# mainboard_v1.net
KiCad netlist of a schematic drawn in EAGLE
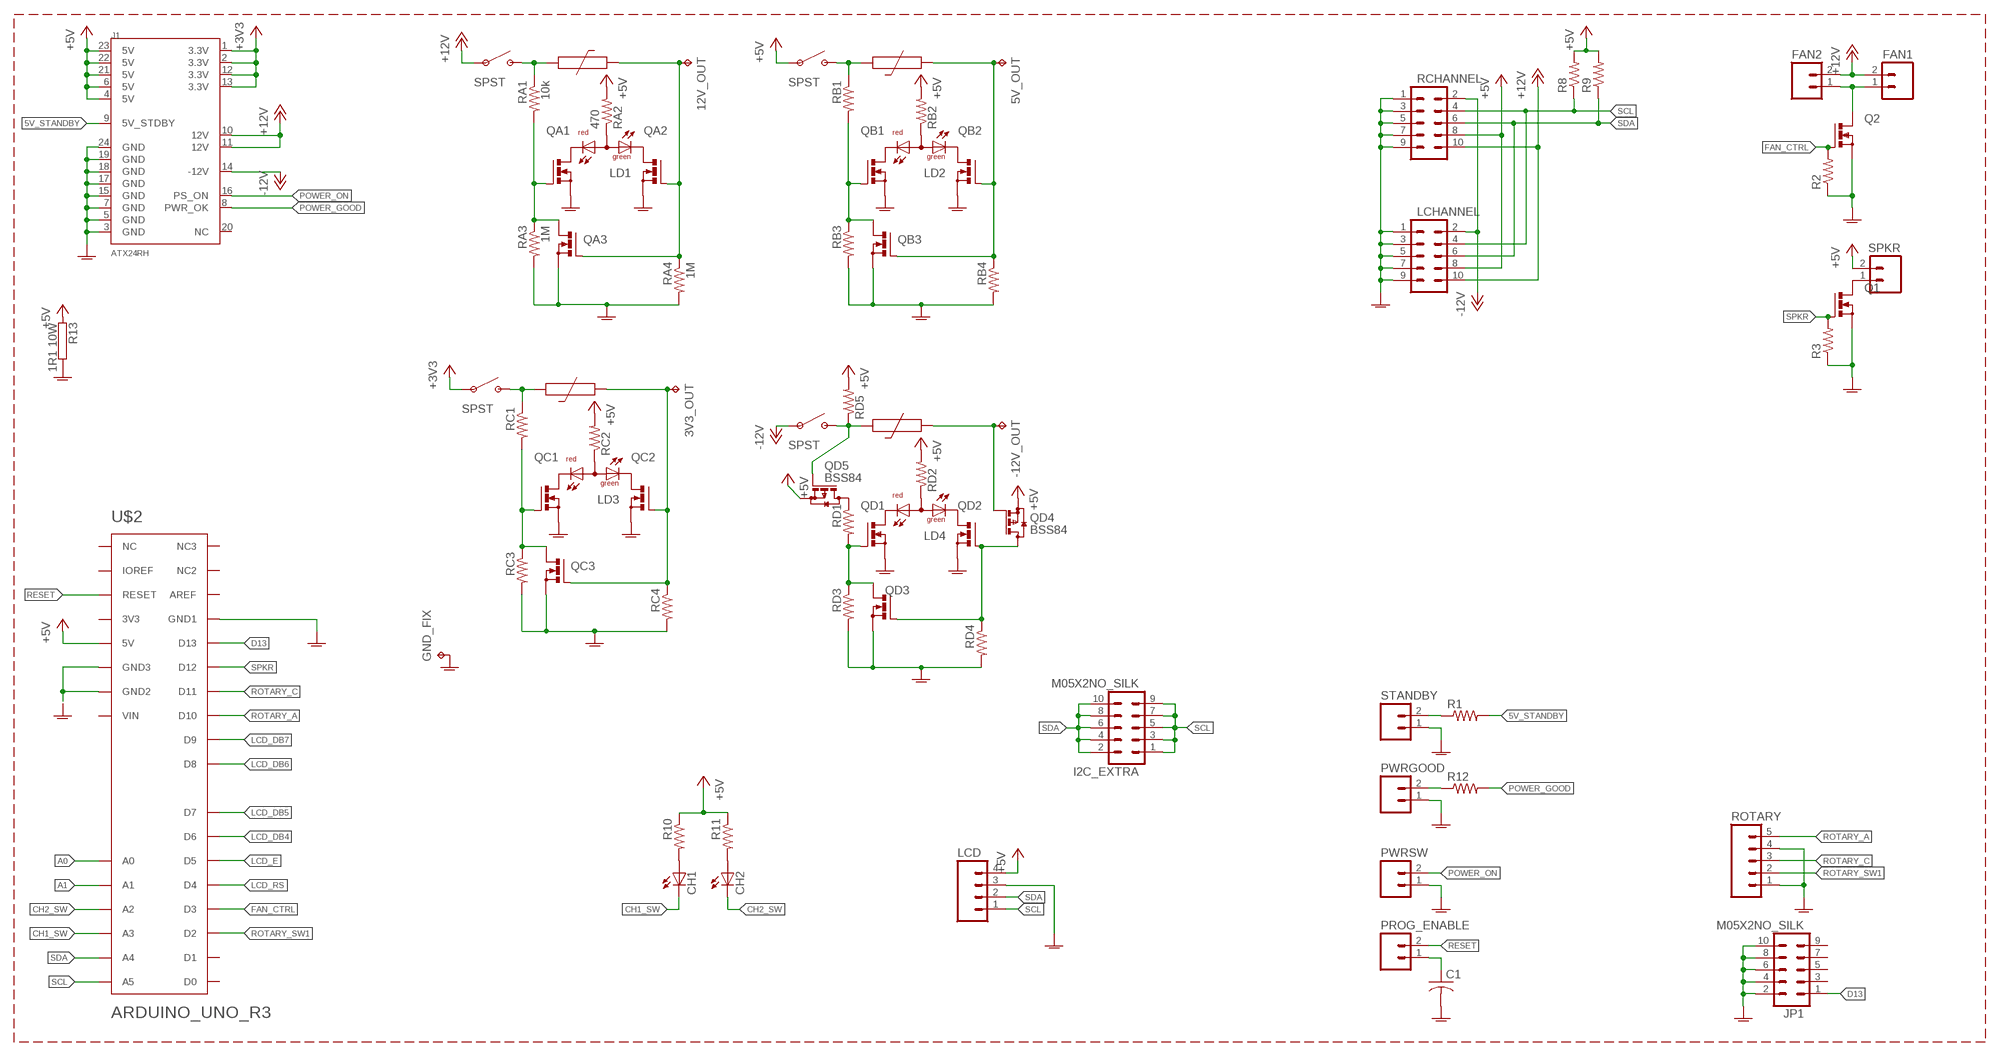
[diagram p0: schematic, sheet 1]

(export (version "E")
  (design (tool "Eeschema 10.0.6"))
  (components
    (comp (ref "-12V_OUT")
      (value "TPPAD1-20")
      (footprint "eagle-import:P1-20")
      (libsource (lib "eagle-import") (part "TPPAD1-20"))
    )
    (comp (ref "3V3_OUT")
      (value "TPPAD1-20")
      (footprint "eagle-import:P1-20")
      (libsource (lib "eagle-import") (part "TPPAD1-20"))
    )
    (comp (ref "5V_OUT")
      (value "TPPAD1-20")
      (footprint "eagle-import:P1-20")
      (libsource (lib "eagle-import") (part "TPPAD1-20"))
    )
    (comp (ref "12V_OUT")
      (value "TPPAD1-20")
      (footprint "eagle-import:P1-20")
      (libsource (lib "eagle-import") (part "TPPAD1-20"))
    )
    (comp (ref "C1")
      (value "C-USC0805")
      (footprint "eagle-import:C0805")
      (libsource (lib "eagle-import") (part "C-USC0805"))
    )
    (comp (ref "CH1")
      (value "LED5MM")
      (footprint "eagle-import:LED5MM")
      (libsource (lib "eagle-import") (part "LED5MM"))
    )
    (comp (ref "CH2")
      (value "LED5MM")
      (footprint "eagle-import:LED5MM")
      (libsource (lib "eagle-import") (part "LED5MM"))
    )
    (comp (ref "FAN1")
      (value "M02PTH")
      (footprint "eagle-import:1X02")
      (libsource (lib "eagle-import") (part "M02PTH"))
    )
    (comp (ref "FAN2")
      (value "M02PTH")
      (footprint "eagle-import:1X02")
      (libsource (lib "eagle-import") (part "M02PTH"))
    )
    (comp (ref "GND_FIX")
      (value "TPPAD1-20")
      (footprint "eagle-import:P1-20")
      (libsource (lib "eagle-import") (part "TPPAD1-20"))
    )
    (comp (ref "I2C_EXTRA")
      (value "M05X2NO_SILK")
      (footprint "eagle-import:2X5_NOSILK")
      (libsource (lib "eagle-import") (part "M05X2NO_SILK"))
    )
    (comp (ref "J1")
      (value "ATX24RH")
      (footprint "eagle-import:ATX24_RIGHT_ANGLE")
      (libsource (lib "eagle-import") (part "ATX24RH"))
    )
    (comp (ref "JP1")
      (value "M05X2NO_SILK")
      (footprint "eagle-import:2X5_NOSILK")
      (libsource (lib "eagle-import") (part "M05X2NO_SILK"))
    )
    (comp (ref "LCD")
      (value "M04")
      (footprint "eagle-import:04P")
      (libsource (lib "eagle-import") (part "M04"))
    )
    (comp (ref "LCHANNEL")
      (value "M05X2SHD")
      (footprint "eagle-import:2X5-SHROUDED")
      (libsource (lib "eagle-import") (part "M05X2SHD"))
    )
    (comp (ref "LD1")
      (value "DUOLED-RG-A")
      (footprint "eagle-import:DUOLED-A-5MM")
      (libsource (lib "eagle-import") (part "DUOLED-RG-A"))
    )
    (comp (ref "LD2")
      (value "DUOLED-RG-A")
      (footprint "eagle-import:DUOLED-A-5MM")
      (libsource (lib "eagle-import") (part "DUOLED-RG-A"))
    )
    (comp (ref "LD3")
      (value "DUOLED-RG-A")
      (footprint "eagle-import:DUOLED-A-5MM")
      (libsource (lib "eagle-import") (part "DUOLED-RG-A"))
    )
    (comp (ref "LD4")
      (value "DUOLED-RG-A")
      (footprint "eagle-import:DUOLED-A-5MM")
      (libsource (lib "eagle-import") (part "DUOLED-RG-A"))
    )
    (comp (ref "PROG_ENABLE")
      (value "M02PTH")
      (footprint "eagle-import:1X02")
      (libsource (lib "eagle-import") (part "M02PTH"))
    )
    (comp (ref "PWRGOOD")
      (value "M02PTH")
      (footprint "eagle-import:1X02")
      (libsource (lib "eagle-import") (part "M02PTH"))
    )
    (comp (ref "PWRSW")
      (value "M02PTH")
      (footprint "eagle-import:1X02")
      (libsource (lib "eagle-import") (part "M02PTH"))
    )
    (comp (ref "Q1")
      (value "2N7002L")
      (footprint "eagle-import:SOT23")
      (libsource (lib "eagle-import") (part "2N7002L"))
    )
    (comp (ref "Q2")
      (value "2N7002L")
      (footprint "eagle-import:SOT23")
      (libsource (lib "eagle-import") (part "2N7002L"))
    )
    (comp (ref "QA1")
      (value "2N7002L")
      (footprint "eagle-import:SOT23")
      (libsource (lib "eagle-import") (part "2N7002L"))
    )
    (comp (ref "QA2")
      (value "2N7002L")
      (footprint "eagle-import:SOT23")
      (libsource (lib "eagle-import") (part "2N7002L"))
    )
    (comp (ref "QA3")
      (value "2N7002L")
      (footprint "eagle-import:SOT23")
      (libsource (lib "eagle-import") (part "2N7002L"))
    )
    (comp (ref "QB1")
      (value "2N7002L")
      (footprint "eagle-import:SOT23")
      (libsource (lib "eagle-import") (part "2N7002L"))
    )
    (comp (ref "QB2")
      (value "2N7002L")
      (footprint "eagle-import:SOT23")
      (libsource (lib "eagle-import") (part "2N7002L"))
    )
    (comp (ref "QB3")
      (value "2N7002L")
      (footprint "eagle-import:SOT23")
      (libsource (lib "eagle-import") (part "2N7002L"))
    )
    (comp (ref "QC1")
      (value "2N7002L")
      (footprint "eagle-import:SOT23")
      (libsource (lib "eagle-import") (part "2N7002L"))
    )
    (comp (ref "QC2")
      (value "2N7002L")
      (footprint "eagle-import:SOT23")
      (libsource (lib "eagle-import") (part "2N7002L"))
    )
    (comp (ref "QC3")
      (value "2N7002L")
      (footprint "eagle-import:SOT23")
      (libsource (lib "eagle-import") (part "2N7002L"))
    )
    (comp (ref "QD1")
      (value "2N7002L")
      (footprint "eagle-import:SOT23")
      (libsource (lib "eagle-import") (part "2N7002L"))
    )
    (comp (ref "QD2")
      (value "2N7002L")
      (footprint "eagle-import:SOT23")
      (libsource (lib "eagle-import") (part "2N7002L"))
    )
    (comp (ref "QD3")
      (value "2N7002L")
      (footprint "eagle-import:SOT23")
      (libsource (lib "eagle-import") (part "2N7002L"))
    )
    (comp (ref "QD4")
      (value "BSS84")
      (footprint "eagle-import:SOT23")
      (libsource (lib "eagle-import") (part "BSS84"))
    )
    (comp (ref "QD5")
      (value "BSS84")
      (footprint "eagle-import:SOT23")
      (libsource (lib "eagle-import") (part "BSS84"))
    )
    (comp (ref "R1")
      (value "R-US_R0805")
      (footprint "eagle-import:R0805")
      (libsource (lib "eagle-import") (part "R-US_R0805"))
    )
    (comp (ref "R2")
      (value "R-US_R0805")
      (footprint "eagle-import:R0805")
      (libsource (lib "eagle-import") (part "R-US_R0805"))
    )
    (comp (ref "R3")
      (value "R-US_R0805")
      (footprint "eagle-import:R0805")
      (libsource (lib "eagle-import") (part "R-US_R0805"))
    )
    (comp (ref "R8")
      (value "R-US_R0805")
      (footprint "eagle-import:R0805")
      (libsource (lib "eagle-import") (part "R-US_R0805"))
    )
    (comp (ref "R9")
      (value "R-US_R0805")
      (footprint "eagle-import:R0805")
      (libsource (lib "eagle-import") (part "R-US_R0805"))
    )
    (comp (ref "R10")
      (value "R-US_R0805")
      (footprint "eagle-import:R0805")
      (libsource (lib "eagle-import") (part "R-US_R0805"))
    )
    (comp (ref "R11")
      (value "R-US_R0805")
      (footprint "eagle-import:R0805")
      (libsource (lib "eagle-import") (part "R-US_R0805"))
    )
    (comp (ref "R12")
      (value "R-US_R0805")
      (footprint "eagle-import:R0805")
      (libsource (lib "eagle-import") (part "R-US_R0805"))
    )
    (comp (ref "R13")
      (value "1R1 10W")
      (footprint "eagle-import:MNS-5")
      (libsource (lib "eagle-import") (part "RMNS-5"))
    )
    (comp (ref "RA1")
      (value "10k")
      (footprint "eagle-import:R0805")
      (libsource (lib "eagle-import") (part "R-US_R0805"))
    )
    (comp (ref "RA2")
      (value "470")
      (footprint "eagle-import:R0805")
      (libsource (lib "eagle-import") (part "R-US_R0805"))
    )
    (comp (ref "RA3")
      (value "1M")
      (footprint "eagle-import:R0805")
      (libsource (lib "eagle-import") (part "R-US_R0805"))
    )
    (comp (ref "RA4")
      (value "1M")
      (footprint "eagle-import:R0805")
      (libsource (lib "eagle-import") (part "R-US_R0805"))
    )
    (comp (ref "RB1")
      (value "R-US_R0805")
      (footprint "eagle-import:R0805")
      (libsource (lib "eagle-import") (part "R-US_R0805"))
    )
    (comp (ref "RB2")
      (value "R-US_R0805")
      (footprint "eagle-import:R0805")
      (libsource (lib "eagle-import") (part "R-US_R0805"))
    )
    (comp (ref "RB3")
      (value "R-US_R0805")
      (footprint "eagle-import:R0805")
      (libsource (lib "eagle-import") (part "R-US_R0805"))
    )
    (comp (ref "RB4")
      (value "R-US_R0805")
      (footprint "eagle-import:R0805")
      (libsource (lib "eagle-import") (part "R-US_R0805"))
    )
    (comp (ref "RC1")
      (value "R-US_R0805")
      (footprint "eagle-import:R0805")
      (libsource (lib "eagle-import") (part "R-US_R0805"))
    )
    (comp (ref "RC2")
      (value "R-US_R0805")
      (footprint "eagle-import:R0805")
      (libsource (lib "eagle-import") (part "R-US_R0805"))
    )
    (comp (ref "RC3")
      (value "R-US_R0805")
      (footprint "eagle-import:R0805")
      (libsource (lib "eagle-import") (part "R-US_R0805"))
    )
    (comp (ref "RC4")
      (value "R-US_R0805")
      (footprint "eagle-import:R0805")
      (libsource (lib "eagle-import") (part "R-US_R0805"))
    )
    (comp (ref "RCHANNEL")
      (value "M05X2SHD")
      (footprint "eagle-import:2X5-SHROUDED")
      (libsource (lib "eagle-import") (part "M05X2SHD"))
    )
    (comp (ref "RD1")
      (value "R-US_R0805")
      (footprint "eagle-import:R0805")
      (libsource (lib "eagle-import") (part "R-US_R0805"))
    )
    (comp (ref "RD2")
      (value "R-US_R0805")
      (footprint "eagle-import:R0805")
      (libsource (lib "eagle-import") (part "R-US_R0805"))
    )
    (comp (ref "RD3")
      (value "R-US_R0805")
      (footprint "eagle-import:R0805")
      (libsource (lib "eagle-import") (part "R-US_R0805"))
    )
    (comp (ref "RD4")
      (value "R-US_R0805")
      (footprint "eagle-import:R0805")
      (libsource (lib "eagle-import") (part "R-US_R0805"))
    )
    (comp (ref "RD5")
      (value "R-US_R0805")
      (footprint "eagle-import:R0805")
      (libsource (lib "eagle-import") (part "R-US_R0805"))
    )
    (comp (ref "ROTARY")
      (value "M05")
      (footprint "eagle-import:05P")
      (libsource (lib "eagle-import") (part "M05"))
    )
    (comp (ref "SPKR")
      (value "M02PTH")
      (footprint "eagle-import:1X02")
      (libsource (lib "eagle-import") (part "M02PTH"))
    )
    (comp (ref "STANDBY")
      (value "M02PTH")
      (footprint "eagle-import:1X02")
      (libsource (lib "eagle-import") (part "M02PTH"))
    )
    (comp (ref "U$1")
      (value "MF-R300")
      (footprint "eagle-import:MR-300")
      (libsource (lib "eagle-import") (part "MF-R300"))
    )
    (comp (ref "U$2")
      (value "ARDUINO_UNO_R3MINIMUM")
      (footprint "eagle-import:ARDUINO_UNO_R3_MIN")
      (libsource (lib "eagle-import") (part "ARDUINO_UNO_R3MINIMUM"))
    )
    (comp (ref "U$3")
      (value "MF-R300")
      (footprint "eagle-import:MR-300")
      (libsource (lib "eagle-import") (part "MF-R300"))
    )
    (comp (ref "U$4")
      (value "MF-R300")
      (footprint "eagle-import:MR-300")
      (libsource (lib "eagle-import") (part "MF-R300"))
    )
    (comp (ref "U$5")
      (value "MF-R300")
      (footprint "eagle-import:MR-300")
      (libsource (lib "eagle-import") (part "MF-R300"))
    )
    (comp (ref "U$6")
      (value "SPST")
      (footprint "eagle-import:2P_REMOTE")
      (libsource (lib "eagle-import") (part "SPST"))
    )
    (comp (ref "U$8")
      (value "SPST")
      (footprint "eagle-import:2P_REMOTE")
      (libsource (lib "eagle-import") (part "SPST"))
    )
    (comp (ref "U$9")
      (value "SPST")
      (footprint "eagle-import:2P_REMOTE")
      (libsource (lib "eagle-import") (part "SPST"))
    )
    (comp (ref "U$10")
      (value "SPST")
      (footprint "eagle-import:2P_REMOTE")
      (libsource (lib "eagle-import") (part "SPST"))
    )
  )
  (nets
    (net (code "1") (name "+3V3") (class "Default")
      (node (ref "J1") (pin "1") (pinfunction "3.3V_1") (pintype "bidirectional"))
      (node (ref "J1") (pin "12") (pinfunction "3.3V_12") (pintype "bidirectional"))
      (node (ref "J1") (pin "13") (pinfunction "3.3V_13") (pintype "bidirectional"))
      (node (ref "J1") (pin "2") (pinfunction "3.3V_2") (pintype "bidirectional"))
      (node (ref "U$9") (pin "1") (pinfunction "P$1_1") (pintype "bidirectional"))
    )
    (net (code "2") (name "+5V") (class "Default")
      (node (ref "J1") (pin "21") (pinfunction "5V_21") (pintype "bidirectional"))
      (node (ref "J1") (pin "22") (pinfunction "5V_22") (pintype "bidirectional"))
      (node (ref "J1") (pin "23") (pinfunction "5V_23") (pintype "bidirectional"))
      (node (ref "J1") (pin "4") (pinfunction "5V_4") (pintype "bidirectional"))
      (node (ref "J1") (pin "6") (pinfunction "5V_6") (pintype "bidirectional"))
      (node (ref "LCD") (pin "4") (pinfunction "4_4") (pintype "passive"))
      (node (ref "LCHANNEL") (pin "8") (pinfunction "8_8") (pintype "passive"))
      (node (ref "QD4") (pin "2") (pinfunction "S_2") (pintype "passive"))
      (node (ref "QD5") (pin "2") (pinfunction "S_2") (pintype "passive"))
      (node (ref "R10") (pin "1") (pinfunction "1_1") (pintype "passive"))
      (node (ref "R11") (pin "1") (pinfunction "1_1") (pintype "passive"))
      (node (ref "R13") (pin "1") (pinfunction "1_1") (pintype "passive"))
      (node (ref "R8") (pin "2") (pinfunction "2_2") (pintype "passive"))
      (node (ref "R9") (pin "2") (pinfunction "2_2") (pintype "passive"))
      (node (ref "RA2") (pin "2") (pinfunction "2_2") (pintype "passive"))
      (node (ref "RB2") (pin "2") (pinfunction "2_2") (pintype "passive"))
      (node (ref "RC2") (pin "2") (pinfunction "2_2") (pintype "passive"))
      (node (ref "RCHANNEL") (pin "8") (pinfunction "8_8") (pintype "passive"))
      (node (ref "RD2") (pin "2") (pinfunction "2_2") (pintype "passive"))
      (node (ref "RD5") (pin "2") (pinfunction "2_2") (pintype "passive"))
      (node (ref "SPKR") (pin "2") (pinfunction "2_2") (pintype "passive"))
      (node (ref "U$2") (pin "5V") (pinfunction "5V_5V") (pintype "bidirectional"))
      (node (ref "U$8") (pin "1") (pinfunction "P$1_1") (pintype "bidirectional"))
    )
    (net (code "3") (name "+12V") (class "Default")
      (node (ref "FAN1") (pin "2") (pinfunction "2_2") (pintype "passive"))
      (node (ref "FAN2") (pin "2") (pinfunction "2_2") (pintype "passive"))
      (node (ref "J1") (pin "10") (pinfunction "12V_10") (pintype "bidirectional"))
      (node (ref "J1") (pin "11") (pinfunction "12V_11") (pintype "bidirectional"))
      (node (ref "LCHANNEL") (pin "10") (pinfunction "10_10") (pintype "passive"))
      (node (ref "RCHANNEL") (pin "10") (pinfunction "10_10") (pintype "passive"))
      (node (ref "U$6") (pin "1") (pinfunction "P$1_1") (pintype "bidirectional"))
    )
    (net (code "4") (name "-12V") (class "Default")
      (node (ref "J1") (pin "14") (pinfunction "-12V_14") (pintype "bidirectional"))
      (node (ref "LCHANNEL") (pin "2") (pinfunction "2_2") (pintype "passive"))
      (node (ref "RCHANNEL") (pin "2") (pinfunction "2_2") (pintype "passive"))
      (node (ref "U$10") (pin "1") (pinfunction "P$1_1") (pintype "bidirectional"))
    )
    (net (code "5") (name "5V_STANDBY") (class "Default")
      (node (ref "J1") (pin "9") (pinfunction "5V_STDBY_9") (pintype "bidirectional"))
      (node (ref "R1") (pin "2") (pinfunction "2_2") (pintype "passive"))
    )
    (net (code "6") (name "A0") (class "Default")
      (node (ref "U$2") (pin "A0") (pinfunction "A0_A0") (pintype "bidirectional"))
    )
    (net (code "7") (name "A1") (class "Default")
      (node (ref "U$2") (pin "A1") (pinfunction "A1_A1") (pintype "bidirectional"))
    )
    (net (code "8") (name "CH1_SW") (class "Default")
      (node (ref "CH1") (pin "K") (pinfunction "C_K") (pintype "passive"))
      (node (ref "U$2") (pin "A3") (pinfunction "A3_A3") (pintype "bidirectional"))
    )
    (net (code "9") (name "CH2_SW") (class "Default")
      (node (ref "CH2") (pin "K") (pinfunction "C_K") (pintype "passive"))
      (node (ref "U$2") (pin "A2") (pinfunction "A2_A2") (pintype "bidirectional"))
    )
    (net (code "10") (name "D13") (class "Default")
      (node (ref "JP1") (pin "1") (pinfunction "1_1") (pintype "passive"))
      (node (ref "U$2") (pin "D13") (pinfunction "D13_D13") (pintype "bidirectional"))
    )
    (net (code "11") (name "FAN_CTRL") (class "Default")
      (node (ref "Q2") (pin "1") (pinfunction "G_1") (pintype "bidirectional"))
      (node (ref "R2") (pin "2") (pinfunction "2_2") (pintype "passive"))
      (node (ref "U$2") (pin "D3") (pinfunction "D3_D3") (pintype "bidirectional"))
    )
    (net (code "12") (name "GNDA") (class "Default")
      (node (ref "C1") (pin "2") (pinfunction "2_2") (pintype "passive"))
      (node (ref "GND_FIX") (pin "TP") (pinfunction "TP_TP") (pintype "input"))
      (node (ref "J1") (pin "15") (pinfunction "GND_15") (pintype "bidirectional"))
      (node (ref "J1") (pin "17") (pinfunction "GND_17") (pintype "bidirectional"))
      (node (ref "J1") (pin "18") (pinfunction "GND_18") (pintype "bidirectional"))
      (node (ref "J1") (pin "19") (pinfunction "GND_19") (pintype "bidirectional"))
      (node (ref "J1") (pin "24") (pinfunction "GND_24") (pintype "bidirectional"))
      (node (ref "J1") (pin "3") (pinfunction "GND_3") (pintype "bidirectional"))
      (node (ref "J1") (pin "5") (pinfunction "GND_5") (pintype "bidirectional"))
      (node (ref "J1") (pin "7") (pinfunction "GND_7") (pintype "bidirectional"))
      (node (ref "JP1") (pin "10") (pinfunction "10_10") (pintype "passive"))
      (node (ref "JP1") (pin "2") (pinfunction "2_2") (pintype "passive"))
      (node (ref "JP1") (pin "4") (pinfunction "4_4") (pintype "passive"))
      (node (ref "JP1") (pin "6") (pinfunction "6_6") (pintype "passive"))
      (node (ref "JP1") (pin "8") (pinfunction "8_8") (pintype "passive"))
      (node (ref "LCD") (pin "3") (pinfunction "3_3") (pintype "passive"))
      (node (ref "LCHANNEL") (pin "1") (pinfunction "1_1") (pintype "passive"))
      (node (ref "LCHANNEL") (pin "3") (pinfunction "3_3") (pintype "passive"))
      (node (ref "LCHANNEL") (pin "5") (pinfunction "5_5") (pintype "passive"))
      (node (ref "LCHANNEL") (pin "7") (pinfunction "7_7") (pintype "passive"))
      (node (ref "LCHANNEL") (pin "9") (pinfunction "9_9") (pintype "passive"))
      (node (ref "PWRGOOD") (pin "1") (pinfunction "1_1") (pintype "passive"))
      (node (ref "PWRSW") (pin "1") (pinfunction "1_1") (pintype "passive"))
      (node (ref "Q1") (pin "2") (pinfunction "S_2") (pintype "bidirectional"))
      (node (ref "Q2") (pin "2") (pinfunction "S_2") (pintype "bidirectional"))
      (node (ref "QA1") (pin "2") (pinfunction "S_2") (pintype "bidirectional"))
      (node (ref "QA2") (pin "2") (pinfunction "S_2") (pintype "bidirectional"))
      (node (ref "QA3") (pin "2") (pinfunction "S_2") (pintype "bidirectional"))
      (node (ref "QB1") (pin "2") (pinfunction "S_2") (pintype "bidirectional"))
      (node (ref "QB2") (pin "2") (pinfunction "S_2") (pintype "bidirectional"))
      (node (ref "QB3") (pin "2") (pinfunction "S_2") (pintype "bidirectional"))
      (node (ref "QC1") (pin "2") (pinfunction "S_2") (pintype "bidirectional"))
      (node (ref "QC2") (pin "2") (pinfunction "S_2") (pintype "bidirectional"))
      (node (ref "QC3") (pin "2") (pinfunction "S_2") (pintype "bidirectional"))
      (node (ref "QD1") (pin "2") (pinfunction "S_2") (pintype "bidirectional"))
      (node (ref "QD2") (pin "2") (pinfunction "S_2") (pintype "bidirectional"))
      (node (ref "QD3") (pin "2") (pinfunction "S_2") (pintype "bidirectional"))
      (node (ref "R13") (pin "2") (pinfunction "2_2") (pintype "passive"))
      (node (ref "R2") (pin "1") (pinfunction "1_1") (pintype "passive"))
      (node (ref "R3") (pin "1") (pinfunction "1_1") (pintype "passive"))
      (node (ref "RA3") (pin "2") (pinfunction "2_2") (pintype "passive"))
      (node (ref "RA4") (pin "2") (pinfunction "2_2") (pintype "passive"))
      (node (ref "RB3") (pin "2") (pinfunction "2_2") (pintype "passive"))
      (node (ref "RB4") (pin "2") (pinfunction "2_2") (pintype "passive"))
      (node (ref "RC3") (pin "2") (pinfunction "2_2") (pintype "passive"))
      (node (ref "RC4") (pin "2") (pinfunction "2_2") (pintype "passive"))
      (node (ref "RCHANNEL") (pin "1") (pinfunction "1_1") (pintype "passive"))
      (node (ref "RCHANNEL") (pin "3") (pinfunction "3_3") (pintype "passive"))
      (node (ref "RCHANNEL") (pin "5") (pinfunction "5_5") (pintype "passive"))
      (node (ref "RCHANNEL") (pin "7") (pinfunction "7_7") (pintype "passive"))
      (node (ref "RCHANNEL") (pin "9") (pinfunction "9_9") (pintype "passive"))
      (node (ref "RD3") (pin "2") (pinfunction "2_2") (pintype "passive"))
      (node (ref "RD4") (pin "2") (pinfunction "2_2") (pintype "passive"))
      (node (ref "ROTARY") (pin "1") (pinfunction "1_1") (pintype "passive"))
      (node (ref "ROTARY") (pin "4") (pinfunction "4_4") (pintype "passive"))
      (node (ref "STANDBY") (pin "1") (pinfunction "1_1") (pintype "passive"))
      (node (ref "U$2") (pin "GND") (pinfunction "GND1_GND") (pintype "bidirectional"))
      (node (ref "U$2") (pin "GND2") (pinfunction "GND2_GND2") (pintype "bidirectional"))
      (node (ref "U$2") (pin "GND3") (pinfunction "GND3_GND3") (pintype "bidirectional"))
    )
    (net (code "13") (name "LCD_DB4") (class "Default")
      (node (ref "U$2") (pin "D6") (pinfunction "D6_D6") (pintype "bidirectional"))
    )
    (net (code "14") (name "LCD_DB5") (class "Default")
      (node (ref "U$2") (pin "D7") (pinfunction "D7_D7") (pintype "bidirectional"))
    )
    (net (code "15") (name "LCD_DB6") (class "Default")
      (node (ref "U$2") (pin "D8") (pinfunction "D8_D8") (pintype "bidirectional"))
    )
    (net (code "16") (name "LCD_DB7") (class "Default")
      (node (ref "U$2") (pin "D9") (pinfunction "D9_D9") (pintype "bidirectional"))
    )
    (net (code "17") (name "LCD_E") (class "Default")
      (node (ref "U$2") (pin "D5") (pinfunction "D5_D5") (pintype "bidirectional"))
    )
    (net (code "18") (name "LCD_RS") (class "Default")
      (node (ref "U$2") (pin "D4") (pinfunction "D4_D4") (pintype "bidirectional"))
    )
    (net (code "19") (name "Net-(C1-Pad1)") (class "Default")
      (node (ref "C1") (pin "1") (pinfunction "1_1") (pintype "passive"))
      (node (ref "PROG_ENABLE") (pin "1") (pinfunction "1_1") (pintype "passive"))
    )
    (net (code "20") (name "Net-(CH1-PadA)") (class "Default")
      (node (ref "CH1") (pin "A") (pinfunction "A_A") (pintype "passive"))
      (node (ref "R10") (pin "2") (pinfunction "2_2") (pintype "passive"))
    )
    (net (code "21") (name "Net-(CH2-PadA)") (class "Default")
      (node (ref "CH2") (pin "A") (pinfunction "A_A") (pintype "passive"))
      (node (ref "R11") (pin "2") (pinfunction "2_2") (pintype "passive"))
    )
    (net (code "22") (name "Net-(LD1-CG)") (class "Default")
      (node (ref "LD1") (pin "CX") (pinfunction "CG_CX") (pintype "passive"))
      (node (ref "QA2") (pin "3") (pinfunction "D_3") (pintype "bidirectional"))
    )
    (net (code "23") (name "Net-(LD1-PadA)") (class "Default")
      (node (ref "LD1") (pin "A") (pinfunction "A_A") (pintype "passive"))
      (node (ref "RA2") (pin "1") (pinfunction "1_1") (pintype "passive"))
    )
    (net (code "24") (name "Net-(LD2-CG)") (class "Default")
      (node (ref "LD2") (pin "CX") (pinfunction "CG_CX") (pintype "passive"))
      (node (ref "QB2") (pin "3") (pinfunction "D_3") (pintype "bidirectional"))
    )
    (net (code "25") (name "Net-(LD2-PadA)") (class "Default")
      (node (ref "LD2") (pin "A") (pinfunction "A_A") (pintype "passive"))
      (node (ref "RB2") (pin "1") (pinfunction "1_1") (pintype "passive"))
    )
    (net (code "26") (name "Net-(LD3-CG)") (class "Default")
      (node (ref "LD3") (pin "CX") (pinfunction "CG_CX") (pintype "passive"))
      (node (ref "QC2") (pin "3") (pinfunction "D_3") (pintype "bidirectional"))
    )
    (net (code "27") (name "Net-(LD3-PadA)") (class "Default")
      (node (ref "LD3") (pin "A") (pinfunction "A_A") (pintype "passive"))
      (node (ref "RC2") (pin "1") (pinfunction "1_1") (pintype "passive"))
    )
    (net (code "28") (name "Net-(LD4-CG)") (class "Default")
      (node (ref "LD4") (pin "CX") (pinfunction "CG_CX") (pintype "passive"))
      (node (ref "QD2") (pin "3") (pinfunction "D_3") (pintype "bidirectional"))
    )
    (net (code "29") (name "Net-(LD4-PadA)") (class "Default")
      (node (ref "LD4") (pin "A") (pinfunction "A_A") (pintype "passive"))
      (node (ref "RD2") (pin "1") (pinfunction "1_1") (pintype "passive"))
    )
    (net (code "30") (name "Net-(PWRGOOD-Pad2)") (class "Default")
      (node (ref "PWRGOOD") (pin "2") (pinfunction "2_2") (pintype "passive"))
      (node (ref "R12") (pin "1") (pinfunction "1_1") (pintype "passive"))
    )
    (net (code "31") (name "Net-(Q1-D)") (class "Default")
      (node (ref "Q1") (pin "3") (pinfunction "D_3") (pintype "bidirectional"))
      (node (ref "SPKR") (pin "1") (pinfunction "1_1") (pintype "passive"))
    )
    (net (code "32") (name "Net-(Q2-D)") (class "Default")
      (node (ref "FAN1") (pin "1") (pinfunction "1_1") (pintype "passive"))
      (node (ref "FAN2") (pin "1") (pinfunction "1_1") (pintype "passive"))
      (node (ref "Q2") (pin "3") (pinfunction "D_3") (pintype "bidirectional"))
    )
    (net (code "33") (name "Net-(QA1-D)") (class "Default")
      (node (ref "LD1") (pin "CR") (pinfunction "CR_CR") (pintype "passive"))
      (node (ref "QA1") (pin "3") (pinfunction "D_3") (pintype "bidirectional"))
    )
    (net (code "34") (name "Net-(QA1-G)") (class "Default")
      (node (ref "QA1") (pin "1") (pinfunction "G_1") (pintype "bidirectional"))
      (node (ref "QA3") (pin "3") (pinfunction "D_3") (pintype "bidirectional"))
      (node (ref "RA1") (pin "2") (pinfunction "2_2") (pintype "passive"))
      (node (ref "RA3") (pin "1") (pinfunction "1_1") (pintype "passive"))
    )
    (net (code "35") (name "Net-(QA2-G)") (class "Default")
      (node (ref "12V_OUT") (pin "TP") (pinfunction "TP_TP") (pintype "input"))
      (node (ref "QA2") (pin "1") (pinfunction "G_1") (pintype "bidirectional"))
      (node (ref "QA3") (pin "1") (pinfunction "G_1") (pintype "bidirectional"))
      (node (ref "RA4") (pin "1") (pinfunction "1_1") (pintype "passive"))
      (node (ref "U$1") (pin "P$1") (pinfunction "1_P$1") (pintype "input"))
    )
    (net (code "36") (name "Net-(QB1-D)") (class "Default")
      (node (ref "LD2") (pin "CR") (pinfunction "CR_CR") (pintype "passive"))
      (node (ref "QB1") (pin "3") (pinfunction "D_3") (pintype "bidirectional"))
    )
    (net (code "37") (name "Net-(QB1-G)") (class "Default")
      (node (ref "QB1") (pin "1") (pinfunction "G_1") (pintype "bidirectional"))
      (node (ref "QB3") (pin "3") (pinfunction "D_3") (pintype "bidirectional"))
      (node (ref "RB1") (pin "2") (pinfunction "2_2") (pintype "passive"))
      (node (ref "RB3") (pin "1") (pinfunction "1_1") (pintype "passive"))
    )
    (net (code "38") (name "Net-(QB2-G)") (class "Default")
      (node (ref "5V_OUT") (pin "TP") (pinfunction "TP_TP") (pintype "input"))
      (node (ref "QB2") (pin "1") (pinfunction "G_1") (pintype "bidirectional"))
      (node (ref "QB3") (pin "1") (pinfunction "G_1") (pintype "bidirectional"))
      (node (ref "RB4") (pin "1") (pinfunction "1_1") (pintype "passive"))
      (node (ref "U$3") (pin "P$2") (pinfunction "2_P$2") (pintype "output"))
    )
    (net (code "39") (name "Net-(QC1-D)") (class "Default")
      (node (ref "LD3") (pin "CR") (pinfunction "CR_CR") (pintype "passive"))
      (node (ref "QC1") (pin "3") (pinfunction "D_3") (pintype "bidirectional"))
    )
    (net (code "40") (name "Net-(QC1-G)") (class "Default")
      (node (ref "QC1") (pin "1") (pinfunction "G_1") (pintype "bidirectional"))
      (node (ref "QC3") (pin "3") (pinfunction "D_3") (pintype "bidirectional"))
      (node (ref "RC1") (pin "2") (pinfunction "2_2") (pintype "passive"))
      (node (ref "RC3") (pin "1") (pinfunction "1_1") (pintype "passive"))
    )
    (net (code "41") (name "Net-(QC2-G)") (class "Default")
      (node (ref "3V3_OUT") (pin "TP") (pinfunction "TP_TP") (pintype "input"))
      (node (ref "QC2") (pin "1") (pinfunction "G_1") (pintype "bidirectional"))
      (node (ref "QC3") (pin "1") (pinfunction "G_1") (pintype "bidirectional"))
      (node (ref "RC4") (pin "1") (pinfunction "1_1") (pintype "passive"))
      (node (ref "U$4") (pin "P$2") (pinfunction "2_P$2") (pintype "output"))
    )
    (net (code "42") (name "Net-(QD1-D)") (class "Default")
      (node (ref "LD4") (pin "CR") (pinfunction "CR_CR") (pintype "passive"))
      (node (ref "QD1") (pin "3") (pinfunction "D_3") (pintype "bidirectional"))
    )
    (net (code "43") (name "Net-(QD1-G)") (class "Default")
      (node (ref "QD1") (pin "1") (pinfunction "G_1") (pintype "bidirectional"))
      (node (ref "QD3") (pin "3") (pinfunction "D_3") (pintype "bidirectional"))
      (node (ref "RD1") (pin "2") (pinfunction "2_2") (pintype "passive"))
      (node (ref "RD3") (pin "1") (pinfunction "1_1") (pintype "passive"))
    )
    (net (code "44") (name "Net-(QD2-G)") (class "Default")
      (node (ref "QD2") (pin "1") (pinfunction "G_1") (pintype "bidirectional"))
      (node (ref "QD3") (pin "1") (pinfunction "G_1") (pintype "bidirectional"))
      (node (ref "QD4") (pin "3") (pinfunction "D_3") (pintype "passive"))
      (node (ref "RD4") (pin "1") (pinfunction "1_1") (pintype "passive"))
    )
    (net (code "45") (name "Net-(QD4-G)") (class "Default")
      (node (ref "-12V_OUT") (pin "TP") (pinfunction "TP_TP") (pintype "input"))
      (node (ref "QD4") (pin "1") (pinfunction "G_1") (pintype "passive"))
      (node (ref "U$5") (pin "P$2") (pinfunction "2_P$2") (pintype "output"))
    )
    (net (code "46") (name "Net-(QD5-D)") (class "Default")
      (node (ref "QD5") (pin "3") (pinfunction "D_3") (pintype "passive"))
      (node (ref "RD1") (pin "1") (pinfunction "1_1") (pintype "passive"))
    )
    (net (code "47") (name "Net-(QD5-G)") (class "Default")
      (node (ref "QD5") (pin "1") (pinfunction "G_1") (pintype "passive"))
      (node (ref "RD5") (pin "1") (pinfunction "1_1") (pintype "passive"))
      (node (ref "U$10") (pin "2") (pinfunction "P$2_2") (pintype "bidirectional"))
      (node (ref "U$5") (pin "P$1") (pinfunction "1_P$1") (pintype "input"))
    )
    (net (code "48") (name "Net-(R1-Pad1)") (class "Default")
      (node (ref "R1") (pin "1") (pinfunction "1_1") (pintype "passive"))
      (node (ref "STANDBY") (pin "2") (pinfunction "2_2") (pintype "passive"))
    )
    (net (code "49") (name "Net-(U$1-2)") (class "Default")
      (node (ref "RA1") (pin "1") (pinfunction "1_1") (pintype "passive"))
      (node (ref "U$1") (pin "P$2") (pinfunction "2_P$2") (pintype "output"))
      (node (ref "U$6") (pin "2") (pinfunction "P$2_2") (pintype "bidirectional"))
    )
    (net (code "50") (name "Net-(U$3-1)") (class "Default")
      (node (ref "RB1") (pin "1") (pinfunction "1_1") (pintype "passive"))
      (node (ref "U$3") (pin "P$1") (pinfunction "1_P$1") (pintype "input"))
      (node (ref "U$8") (pin "2") (pinfunction "P$2_2") (pintype "bidirectional"))
    )
    (net (code "51") (name "Net-(U$4-1)") (class "Default")
      (node (ref "RC1") (pin "1") (pinfunction "1_1") (pintype "passive"))
      (node (ref "U$4") (pin "P$1") (pinfunction "1_P$1") (pintype "input"))
      (node (ref "U$9") (pin "2") (pinfunction "P$2_2") (pintype "bidirectional"))
    )
    (net (code "52") (name "POWER_GOOD") (class "Default")
      (node (ref "J1") (pin "8") (pinfunction "PWR_OK_8") (pintype "bidirectional"))
      (node (ref "R12") (pin "2") (pinfunction "2_2") (pintype "passive"))
    )
    (net (code "53") (name "POWER_ON") (class "Default")
      (node (ref "J1") (pin "16") (pinfunction "PS_ON_16") (pintype "bidirectional"))
      (node (ref "PWRSW") (pin "2") (pinfunction "2_2") (pintype "passive"))
    )
    (net (code "54") (name "RESET") (class "Default")
      (node (ref "PROG_ENABLE") (pin "2") (pinfunction "2_2") (pintype "passive"))
      (node (ref "U$2") (pin "RESET") (pinfunction "RESET_RESET") (pintype "bidirectional"))
    )
    (net (code "55") (name "ROTARY_A") (class "Default")
      (node (ref "ROTARY") (pin "5") (pinfunction "5_5") (pintype "passive"))
      (node (ref "U$2") (pin "D10") (pinfunction "D10_D10") (pintype "bidirectional"))
    )
    (net (code "56") (name "ROTARY_C") (class "Default")
      (node (ref "ROTARY") (pin "3") (pinfunction "3_3") (pintype "passive"))
      (node (ref "U$2") (pin "D11") (pinfunction "D11_D11") (pintype "bidirectional"))
    )
    (net (code "57") (name "ROTARY_SW1") (class "Default")
      (node (ref "ROTARY") (pin "2") (pinfunction "2_2") (pintype "passive"))
      (node (ref "U$2") (pin "D2") (pinfunction "D2_D2") (pintype "bidirectional"))
    )
    (net (code "58") (name "SCL") (class "Default")
      (node (ref "I2C_EXTRA") (pin "1") (pinfunction "1_1") (pintype "passive"))
      (node (ref "I2C_EXTRA") (pin "3") (pinfunction "3_3") (pintype "passive"))
      (node (ref "I2C_EXTRA") (pin "5") (pinfunction "5_5") (pintype "passive"))
      (node (ref "I2C_EXTRA") (pin "7") (pinfunction "7_7") (pintype "passive"))
      (node (ref "I2C_EXTRA") (pin "9") (pinfunction "9_9") (pintype "passive"))
      (node (ref "LCD") (pin "1") (pinfunction "1_1") (pintype "passive"))
      (node (ref "LCHANNEL") (pin "4") (pinfunction "4_4") (pintype "passive"))
      (node (ref "R8") (pin "1") (pinfunction "1_1") (pintype "passive"))
      (node (ref "RCHANNEL") (pin "4") (pinfunction "4_4") (pintype "passive"))
      (node (ref "U$2") (pin "A5") (pinfunction "A5_A5") (pintype "bidirectional"))
    )
    (net (code "59") (name "SDA") (class "Default")
      (node (ref "I2C_EXTRA") (pin "10") (pinfunction "10_10") (pintype "passive"))
      (node (ref "I2C_EXTRA") (pin "2") (pinfunction "2_2") (pintype "passive"))
      (node (ref "I2C_EXTRA") (pin "4") (pinfunction "4_4") (pintype "passive"))
      (node (ref "I2C_EXTRA") (pin "6") (pinfunction "6_6") (pintype "passive"))
      (node (ref "I2C_EXTRA") (pin "8") (pinfunction "8_8") (pintype "passive"))
      (node (ref "LCD") (pin "2") (pinfunction "2_2") (pintype "passive"))
      (node (ref "LCHANNEL") (pin "6") (pinfunction "6_6") (pintype "passive"))
      (node (ref "R9") (pin "1") (pinfunction "1_1") (pintype "passive"))
      (node (ref "RCHANNEL") (pin "6") (pinfunction "6_6") (pintype "passive"))
      (node (ref "U$2") (pin "A4") (pinfunction "A4_A4") (pintype "bidirectional"))
    )
    (net (code "60") (name "SPKR") (class "Default")
      (node (ref "Q1") (pin "1") (pinfunction "G_1") (pintype "bidirectional"))
      (node (ref "R3") (pin "2") (pinfunction "2_2") (pintype "passive"))
      (node (ref "U$2") (pin "D12") (pinfunction "D12_D12") (pintype "bidirectional"))
    )
    (net (code "61") (name "unconnected-(J1-NC-Pad20)") (class "Default")
      (node (ref "J1") (pin "20") (pinfunction "NC_20") (pintype "bidirectional"))
    )
    (net (code "62") (name "unconnected-(JP1-Pad3)") (class "Default")
      (node (ref "JP1") (pin "3") (pinfunction "3_3") (pintype "passive"))
    )
    (net (code "63") (name "unconnected-(JP1-Pad5)") (class "Default")
      (node (ref "JP1") (pin "5") (pinfunction "5_5") (pintype "passive"))
    )
    (net (code "64") (name "unconnected-(JP1-Pad7)") (class "Default")
      (node (ref "JP1") (pin "7") (pinfunction "7_7") (pintype "passive"))
    )
    (net (code "65") (name "unconnected-(JP1-Pad9)") (class "Default")
      (node (ref "JP1") (pin "9") (pinfunction "9_9") (pintype "passive"))
    )
    (net (code "66") (name "unconnected-(U$2-NC-PadP$9)") (class "Default")
      (node (ref "U$2") (pin "P$9") (pinfunction "NC_P$9") (pintype "bidirectional"))
    )
    (net (code "67") (name "unconnected-(U$2-NC2-PadP$10)") (class "Default")
      (node (ref "U$2") (pin "P$10") (pinfunction "NC2_P$10") (pintype "bidirectional"))
    )
    (net (code "68") (name "unconnected-(U$2-NC3-PadP$19)") (class "Default")
      (node (ref "U$2") (pin "P$19") (pinfunction "NC3_P$19") (pintype "bidirectional"))
    )
    (net (code "69") (name "unconnected-(U$2-Pad3V3)") (class "Default")
      (node (ref "U$2") (pin "3V3") (pinfunction "3V3_3V3") (pintype "bidirectional"))
    )
    (net (code "70") (name "unconnected-(U$2-PadAREF)") (class "Default")
      (node (ref "U$2") (pin "AREF") (pinfunction "AREF_AREF") (pintype "bidirectional"))
    )
    (net (code "71") (name "unconnected-(U$2-PadD0)") (class "Default")
      (node (ref "U$2") (pin "D0") (pinfunction "D0_D0") (pintype "bidirectional"))
    )
    (net (code "72") (name "unconnected-(U$2-PadD1)") (class "Default")
      (node (ref "U$2") (pin "D1") (pinfunction "D1_D1") (pintype "bidirectional"))
    )
    (net (code "73") (name "unconnected-(U$2-PadIOREF)") (class "Default")
      (node (ref "U$2") (pin "IOREF") (pinfunction "IOREF_IOREF") (pintype "bidirectional"))
    )
    (net (code "74") (name "unconnected-(U$2-PadVIN)") (class "Default")
      (node (ref "U$2") (pin "VIN") (pinfunction "VIN_VIN") (pintype "bidirectional"))
    )
  )
)
